# Super-Regenerative-FM-Alt.net
KiCad netlist of a schematic drawn in EAGLE
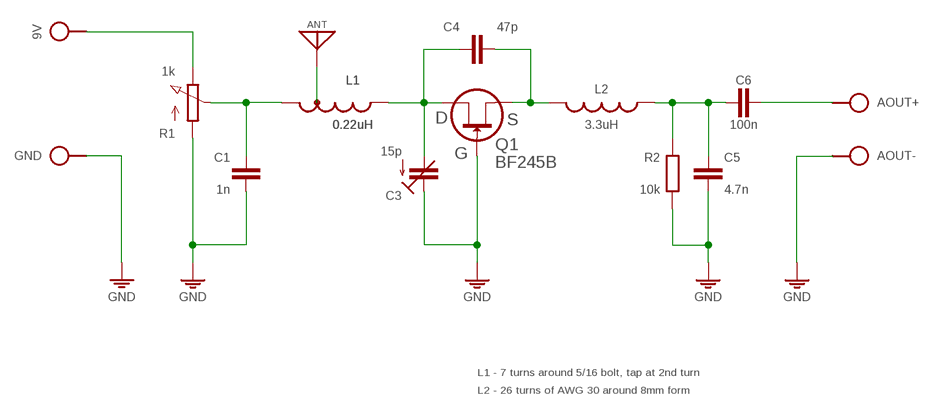
[diagram p0: schematic, sheet 1]

(export (version "E")
  (design (tool "Eeschema 10.0.6"))
  (components
    (comp (ref "9V")
      (value "SPAD")
      (footprint "eagle-import:SPAD")
      (libsource (lib "eagle-import") (part "SPAD"))
    )
    (comp (ref "ANT")
      (value "ANT")
      (footprint "eagle-import:SPAD")
      (libsource (lib "eagle-import") (part "ANT"))
    )
    (comp (ref "AOUT+")
      (value "SPAD")
      (footprint "eagle-import:SPAD")
      (libsource (lib "eagle-import") (part "SPAD"))
    )
    (comp (ref "AOUT-")
      (value "SPAD")
      (footprint "eagle-import:SPAD")
      (libsource (lib "eagle-import") (part "SPAD"))
    )
    (comp (ref "C1")
      (value "1n")
      (footprint "eagle-import:C050-020X036_V")
      (libsource (lib "eagle-import") (part "C050-020X036/V"))
    )
    (comp (ref "C3")
      (value "15p")
      (footprint "eagle-import:TRIM-2222-808")
      (libsource (lib "eagle-import") (part "C-TR-PH201272222-808-2PIN"))
    )
    (comp (ref "C4")
      (value "47p")
      (footprint "eagle-import:C050-020X036")
      (libsource (lib "eagle-import") (part "C050-020X036"))
    )
    (comp (ref "C5")
      (value "4.7n")
      (footprint "eagle-import:C050-020X036")
      (libsource (lib "eagle-import") (part "C050-020X036"))
    )
    (comp (ref "C6")
      (value "100n")
      (footprint "eagle-import:C050-020X036")
      (libsource (lib "eagle-import") (part "C050-020X036"))
    )
    (comp (ref "GND")
      (value "SPAD")
      (footprint "eagle-import:SPAD")
      (libsource (lib "eagle-import") (part "SPAD"))
    )
    (comp (ref "L1")
      (value "0.22uH")
      (footprint "eagle-import:L-08_20V-TAP1")
      (libsource (lib "eagle-import") (part "L-TAP108/7V"))
    )
    (comp (ref "L2")
      (value "3.3uH")
      (footprint "eagle-import:L-BODY")
      (libsource (lib "eagle-import") (part "L-BODY"))
    )
    (comp (ref "Q1")
      (value "BF245B")
      (footprint "eagle-import:TO92")
      (libsource (lib "eagle-import") (part "BF245B"))
    )
    (comp (ref "R1")
      (value "1k")
      (footprint "eagle-import:POT-V")
      (libsource (lib "eagle-import") (part "POT-V"))
    )
    (comp (ref "R2")
      (value "10k")
      (footprint "eagle-import:0204_10")
      (libsource (lib "eagle-import") (part "R0204/10"))
    )
  )
  (nets
    (net (code "1") (name "GND") (class "Default")
      (node (ref "AOUT-") (pin "1") (pinfunction "P$1_1") (pintype "bidirectional"))
      (node (ref "C1") (pin "2") (pinfunction "2_2") (pintype "passive"))
      (node (ref "C3") (pin "1") (pinfunction "E_1") (pintype "passive"))
      (node (ref "C5") (pin "2") (pinfunction "2_2") (pintype "passive"))
      (node (ref "GND") (pin "1") (pinfunction "P$1_1") (pintype "bidirectional"))
      (node (ref "Q1") (pin "1") (pinfunction "G_1") (pintype "passive"))
      (node (ref "R1") (pin "A") (pinfunction "A_A") (pintype "passive"))
      (node (ref "R2") (pin "1") (pinfunction "1_1") (pintype "passive"))
    )
    (net (code "2") (name "Net-(9V-P$1)") (class "Default")
      (node (ref "9V") (pin "1") (pinfunction "P$1_1") (pintype "bidirectional"))
      (node (ref "R1") (pin "E") (pinfunction "E_E") (pintype "passive"))
    )
    (net (code "3") (name "Net-(ANT-Pad1)") (class "Default")
      (node (ref "ANT") (pin "1") (pinfunction "1_1") (pintype "output"))
      (node (ref "L1") (pin "T") (pinfunction "T_T") (pintype "passive"))
    )
    (net (code "4") (name "Net-(AOUT+-P$1)") (class "Default")
      (node (ref "AOUT+") (pin "1") (pinfunction "P$1_1") (pintype "bidirectional"))
      (node (ref "C6") (pin "2") (pinfunction "2_2") (pintype "passive"))
    )
    (net (code "5") (name "Net-(C1-Pad1)") (class "Default")
      (node (ref "C1") (pin "1") (pinfunction "1_1") (pintype "passive"))
      (node (ref "L1") (pin "1") (pinfunction "1_1") (pintype "passive"))
      (node (ref "R1") (pin "S") (pinfunction "S_S") (pintype "passive"))
    )
    (net (code "6") (name "Net-(C3-A)") (class "Default")
      (node (ref "C3") (pin "2") (pinfunction "A_2") (pintype "passive"))
      (node (ref "C4") (pin "1") (pinfunction "1_1") (pintype "passive"))
      (node (ref "L1") (pin "2") (pinfunction "2_2") (pintype "passive"))
      (node (ref "Q1") (pin "3") (pinfunction "D_3") (pintype "passive"))
    )
    (net (code "7") (name "Net-(L2-1)") (class "Default")
      (node (ref "C5") (pin "1") (pinfunction "1_1") (pintype "passive"))
      (node (ref "C6") (pin "1") (pinfunction "1_1") (pintype "passive"))
      (node (ref "L2") (pin "2") (pinfunction "1_2") (pintype "passive"))
      (node (ref "R2") (pin "2") (pinfunction "2_2") (pintype "passive"))
    )
    (net (code "8") (name "Net-(L2-2)") (class "Default")
      (node (ref "C4") (pin "2") (pinfunction "2_2") (pintype "passive"))
      (node (ref "L2") (pin "3") (pinfunction "2_3") (pintype "passive"))
      (node (ref "Q1") (pin "2") (pinfunction "S_2") (pintype "passive"))
    )
  )
)
